# Sheet1.net
KiCad netlist of a schematic drawn in Altium Designer
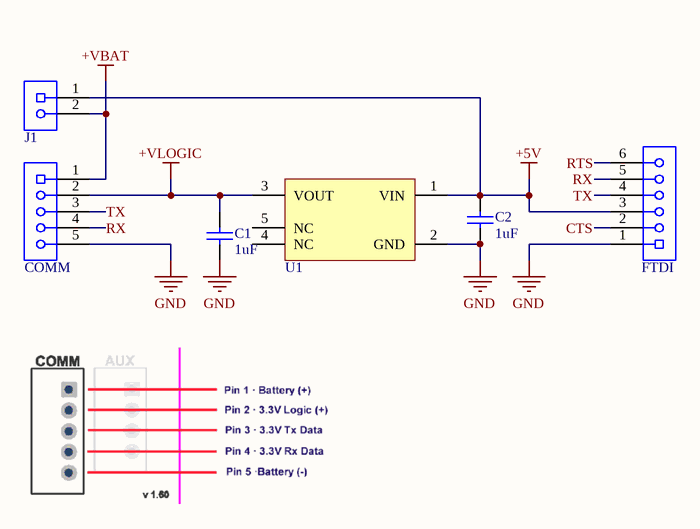
[diagram p0: Sheet1.SchDoc]

(export (version "E")
  (design (tool "Eeschema 10.0.6"))
  (components
    (comp (ref "C1")
      (value "1uF")
      (footprint "CAPC1608X10N")
      (description "Cap Ceramic 1uF 10V X5R 10% SMD 0603 85°C Paper T/R")
      (fields (field (name "TOLERANCE") "10%") (field (name "VOLTAGE") "10V"))
      (libsource (lib "UWA Aerospace") (part "C0603C104M5RACTU"))
    )
    (comp (ref "C2")
      (value "1uF")
      (footprint "CAPC1608X10N")
      (description "Cap Ceramic 1uF 10V X5R 10% SMD 0603 85°C Paper T/R")
      (fields (field (name "TOLERANCE") "10%") (field (name "VOLTAGE") "10V"))
      (libsource (lib "UWA Aerospace") (part "C0603C104M5RACTU"))
    )
    (comp (ref "COMM")
      (value "DF3-5S-2DSA(25)")
      (footprint "DF3-5S-2DSA(25)-Footprint-1")
      (description "Board-to-Cable Connector (Terminal 1 Row Type) with 2-mm Pitch - DF3 Series (HIROSE ELECTRIC)")
      (libsource (lib "UWA Aerospace") (part "Connector - 1x5 Single Sided"))
    )
    (comp (ref "FTDI")
      (value "68000-406HLF")
      (footprint "68000-406HLF-Footprint-1")
      (description "CONN HEADER 6POS .100 STR TIN")
      (libsource (lib "UWA Aerospace") (part "68000-406HLF"))
    )
    (comp (ref "J1")
      (value "22-28-4020")
      (footprint "22-28-4020-Footprint-1")
      (description "KK 254 Breakaway Header, Vertical, 2 Circuits, Tin (Sn) Plating, Mating Pin Length 6.09mm 2 POS")
      (libsource (lib "UWA Aerospace") (part "22-28-4020"))
    )
    (comp (ref "U1")
      (value "AP7370-33WW-7")
      (footprint "SOT95P285X140-5N")
      (description "LDO Regulator Pos 3.3V 0.3A 5-Pin SOT-25 T/R")
      (libsource (lib "UWA Aerospace") (part "AP7370-33WW-7-Symbol-1"))
    )
  )
  (nets
    (net (code "1") (name "+5V") (class "Default")
      (node (ref "C2") (pin "2") (pinfunction "2_2") (pintype "passive"))
      (node (ref "FTDI") (pin "3") (pinfunction "3_3") (pintype "passive"))
      (node (ref "J1") (pin "1") (pinfunction "1_1") (pintype "passive"))
      (node (ref "U1") (pin "1") (pinfunction "VIN_1") (pintype "power_in"))
    )
    (net (code "2") (name "+VBAT") (class "Default")
      (node (ref "COMM") (pin "1") (pinfunction "1_1") (pintype "passive"))
      (node (ref "J1") (pin "2") (pinfunction "2_2") (pintype "passive"))
    )
    (net (code "3") (name "+VLOGIC") (class "Default")
      (node (ref "C1") (pin "2") (pinfunction "2_2") (pintype "passive"))
      (node (ref "COMM") (pin "2") (pinfunction "2_2") (pintype "passive"))
      (node (ref "U1") (pin "3") (pinfunction "VOUT_3") (pintype "power_in"))
    )
    (net (code "4") (name "/CTS") (class "Default")
      (node (ref "FTDI") (pin "2") (pinfunction "2_2") (pintype "passive"))
    )
    (net (code "5") (name "/RTS") (class "Default")
      (node (ref "FTDI") (pin "6") (pinfunction "6_6") (pintype "passive"))
    )
    (net (code "6") (name "/RX") (class "Default")
      (node (ref "COMM") (pin "4") (pinfunction "4_4") (pintype "passive"))
      (node (ref "FTDI") (pin "5") (pinfunction "5_5") (pintype "passive"))
    )
    (net (code "7") (name "/TX") (class "Default")
      (node (ref "COMM") (pin "3") (pinfunction "3_3") (pintype "passive"))
      (node (ref "FTDI") (pin "4") (pinfunction "4_4") (pintype "passive"))
    )
    (net (code "8") (name "GND") (class "Default")
      (node (ref "C1") (pin "1") (pinfunction "1_1") (pintype "passive"))
      (node (ref "C2") (pin "1") (pinfunction "1_1") (pintype "passive"))
      (node (ref "COMM") (pin "5") (pinfunction "5_5") (pintype "passive"))
      (node (ref "FTDI") (pin "1") (pinfunction "1_1") (pintype "passive"))
      (node (ref "U1") (pin "2") (pinfunction "GND_2") (pintype "power_in"))
    )
    (net (code "9") (name "unconnected-(U1-NC-Pad4)") (class "Default")
      (node (ref "U1") (pin "4") (pinfunction "NC_4") (pintype "passive"))
    )
    (net (code "10") (name "unconnected-(U1-NC-Pad5)") (class "Default")
      (node (ref "U1") (pin "5") (pinfunction "NC_5") (pintype "passive"))
    )
  )
)
